# licheepi_nano_pcb.net
KiCad netlist of a schematic drawn in Altium Designer
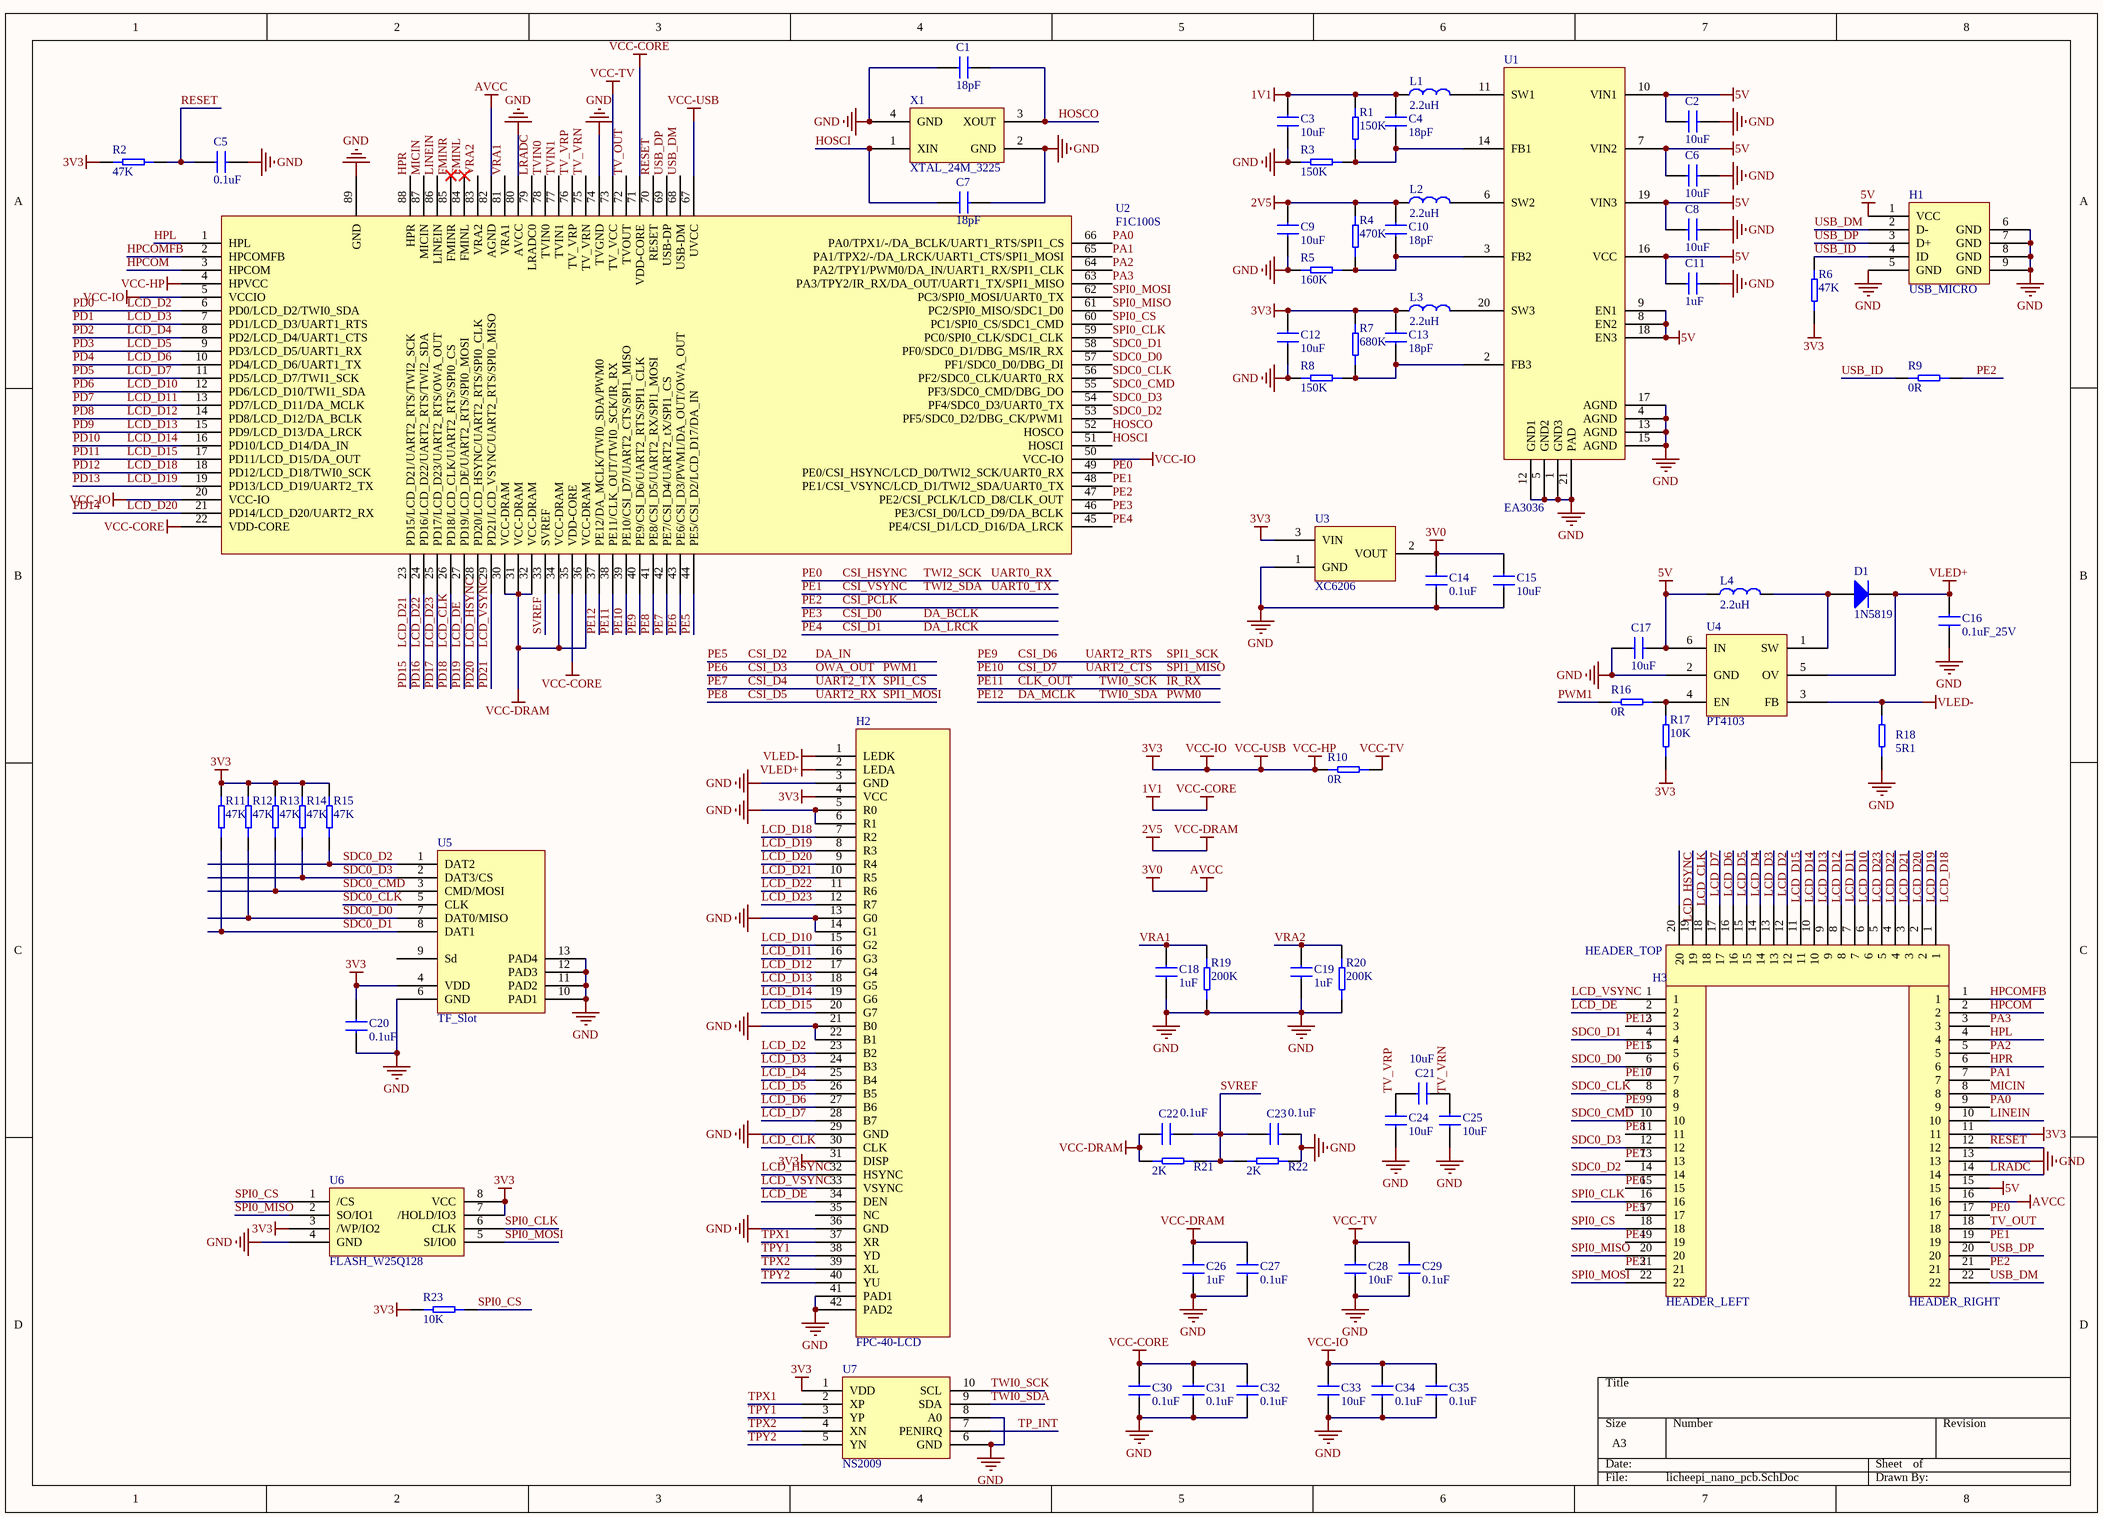
[diagram p0: licheepi_nano_pcb.SchDoc]

(export (version "E")
  (design (tool "Eeschema 10.0.6"))
  (components
    (comp (ref "C1")
      (value "18pF")
      (footprint "0402C")
      (description "SMD-CAP")
      (libsource (lib "licheepi_nano_pcb") (part "CAP"))
    )
    (comp (ref "C2")
      (value "10uF")
      (footprint "0402C")
      (description "SMD-CAP")
      (libsource (lib "licheepi_nano_pcb") (part "CAP"))
    )
    (comp (ref "C3")
      (value "10uF")
      (footprint "0402C")
      (description "SMD-CAP")
      (libsource (lib "licheepi_nano_pcb") (part "CAP"))
    )
    (comp (ref "C4")
      (value "18pF")
      (footprint "0402C")
      (description "SMD-CAP")
      (libsource (lib "licheepi_nano_pcb") (part "CAP"))
    )
    (comp (ref "C5")
      (value "0.1uF")
      (footprint "0402C")
      (description "SMD-CAP")
      (libsource (lib "licheepi_nano_pcb") (part "CAP"))
    )
    (comp (ref "C6")
      (value "10uF")
      (footprint "0402C")
      (description "SMD-CAP")
      (libsource (lib "licheepi_nano_pcb") (part "CAP"))
    )
    (comp (ref "C7")
      (value "18pF")
      (footprint "0402C")
      (description "SMD-CAP")
      (libsource (lib "licheepi_nano_pcb") (part "CAP"))
    )
    (comp (ref "C8")
      (value "10uF")
      (footprint "0402C")
      (description "SMD-CAP")
      (libsource (lib "licheepi_nano_pcb") (part "CAP"))
    )
    (comp (ref "C9")
      (value "10uF")
      (footprint "0402C")
      (description "SMD-CAP")
      (libsource (lib "licheepi_nano_pcb") (part "CAP"))
    )
    (comp (ref "C10")
      (value "18pF")
      (footprint "0402C")
      (description "SMD-CAP")
      (libsource (lib "licheepi_nano_pcb") (part "CAP"))
    )
    (comp (ref "C11")
      (value "1uF")
      (footprint "0402C")
      (description "SMD-CAP")
      (libsource (lib "licheepi_nano_pcb") (part "CAP"))
    )
    (comp (ref "C12")
      (value "10uF")
      (footprint "0402C")
      (description "SMD-CAP")
      (libsource (lib "licheepi_nano_pcb") (part "CAP"))
    )
    (comp (ref "C13")
      (value "18pF")
      (footprint "0402C")
      (description "SMD-CAP")
      (libsource (lib "licheepi_nano_pcb") (part "CAP"))
    )
    (comp (ref "C14")
      (value "0.1uF")
      (footprint "0402C")
      (description "SMD-CAP")
      (libsource (lib "licheepi_nano_pcb") (part "CAP"))
    )
    (comp (ref "C15")
      (value "10uF")
      (footprint "0402C")
      (description "SMD-CAP")
      (libsource (lib "licheepi_nano_pcb") (part "CAP"))
    )
    (comp (ref "C16")
      (value "0.1uF_25V")
      (footprint "0402C")
      (description "SMD-CAP")
      (libsource (lib "licheepi_nano_pcb") (part "CAP"))
    )
    (comp (ref "C17")
      (value "10uF")
      (footprint "0402C")
      (description "SMD-CAP")
      (libsource (lib "licheepi_nano_pcb") (part "CAP"))
    )
    (comp (ref "C18")
      (value "1uF")
      (footprint "0402C")
      (description "SMD-CAP")
      (libsource (lib "licheepi_nano_pcb") (part "CAP"))
    )
    (comp (ref "C19")
      (value "1uF")
      (footprint "0402C")
      (description "SMD-CAP")
      (libsource (lib "licheepi_nano_pcb") (part "CAP"))
    )
    (comp (ref "C20")
      (value "0.1uF")
      (footprint "0402C")
      (description "SMD-CAP")
      (libsource (lib "licheepi_nano_pcb") (part "CAP"))
    )
    (comp (ref "C21")
      (value "10uF")
      (footprint "0402C")
      (description "SMD-CAP")
      (libsource (lib "licheepi_nano_pcb") (part "CAP"))
    )
    (comp (ref "C22")
      (value "0.1uF")
      (footprint "0402C")
      (description "SMD-CAP")
      (libsource (lib "licheepi_nano_pcb") (part "CAP"))
    )
    (comp (ref "C23")
      (value "0.1uF")
      (footprint "0402C")
      (description "SMD-CAP")
      (libsource (lib "licheepi_nano_pcb") (part "CAP"))
    )
    (comp (ref "C24")
      (value "10uF")
      (footprint "0402C")
      (description "SMD-CAP")
      (libsource (lib "licheepi_nano_pcb") (part "CAP"))
    )
    (comp (ref "C25")
      (value "10uF")
      (footprint "0402C")
      (description "SMD-CAP")
      (libsource (lib "licheepi_nano_pcb") (part "CAP"))
    )
    (comp (ref "C26")
      (value "1uF")
      (footprint "0402C")
      (description "SMD-CAP")
      (libsource (lib "licheepi_nano_pcb") (part "CAP"))
    )
    (comp (ref "C27")
      (value "0.1uF")
      (footprint "0402C")
      (description "SMD-CAP")
      (libsource (lib "licheepi_nano_pcb") (part "CAP"))
    )
    (comp (ref "C28")
      (value "10uF")
      (footprint "0402C")
      (description "SMD-CAP")
      (libsource (lib "licheepi_nano_pcb") (part "CAP"))
    )
    (comp (ref "C29")
      (value "0.1uF")
      (footprint "0402C")
      (description "SMD-CAP")
      (libsource (lib "licheepi_nano_pcb") (part "CAP"))
    )
    (comp (ref "C30")
      (value "0.1uF")
      (footprint "0402C")
      (description "SMD-CAP")
      (libsource (lib "licheepi_nano_pcb") (part "CAP"))
    )
    (comp (ref "C31")
      (value "0.1uF")
      (footprint "0402C")
      (description "SMD-CAP")
      (libsource (lib "licheepi_nano_pcb") (part "CAP"))
    )
    (comp (ref "C32")
      (value "0.1uF")
      (footprint "0402C")
      (description "SMD-CAP")
      (libsource (lib "licheepi_nano_pcb") (part "CAP"))
    )
    (comp (ref "C33")
      (value "10uF")
      (footprint "0402C")
      (description "SMD-CAP")
      (libsource (lib "licheepi_nano_pcb") (part "CAP"))
    )
    (comp (ref "C34")
      (value "0.1uF")
      (footprint "0402C")
      (description "SMD-CAP")
      (libsource (lib "licheepi_nano_pcb") (part "CAP"))
    )
    (comp (ref "C35")
      (value "0.1uF")
      (footprint "0402C")
      (description "SMD-CAP")
      (libsource (lib "licheepi_nano_pcb") (part "CAP"))
    )
    (comp (ref "D1")
      (value "1N5819")
      (footprint "SOD123")
      (libsource (lib "licheepi_nano_pcb") (part "1N5819"))
    )
    (comp (ref "H1")
      (value "USB_MICRO")
      (footprint "USB_MICRO_insert")
      (libsource (lib "licheepi_nano_pcb") (part "USB_MICRO"))
    )
    (comp (ref "H2")
      (value "FPC-40-LCD")
      (footprint "FPC-40P-0.5")
      (libsource (lib "licheepi_nano_pcb") (part "FPC-40-LCD"))
    )
    (comp (ref "H3")
      (value "HEADER_TOP")
      (footprint "SIP20_1.27_half")
      (libsource (lib "licheepi_nano_pcb") (part "HEADER_TOP"))
    )
    (comp (ref "H4")
      (value "HEADER_LEFT")
      (footprint "SIP22_10_1.27-mir")
      (libsource (lib "licheepi_nano_pcb") (part "HEADER_LEFT"))
    )
    (comp (ref "H5")
      (value "HEADER_RIGHT")
      (footprint "SIP22_10_1.27")
      (libsource (lib "licheepi_nano_pcb") (part "HEADER_RIGHT"))
    )
    (comp (ref "L1")
      (value "2.2uH")
      (footprint "CD32")
      (description "电感")
      (libsource (lib "licheepi_nano_pcb") (part "L1"))
    )
    (comp (ref "L2")
      (value "2.2uH")
      (footprint "CD32")
      (description "电感")
      (libsource (lib "licheepi_nano_pcb") (part "L1"))
    )
    (comp (ref "L3")
      (value "2.2uH")
      (footprint "CD32")
      (description "电感")
      (libsource (lib "licheepi_nano_pcb") (part "L1"))
    )
    (comp (ref "L4")
      (value "2.2uH")
      (footprint "CD32")
      (description "电感")
      (libsource (lib "licheepi_nano_pcb") (part "L1"))
    )
    (comp (ref "R1") (value "150K") (footprint "0402R") (libsource (lib "licheepi_nano_pcb") (part "R")))
    (comp (ref "R2") (value "47K") (footprint "0402R") (libsource (lib "licheepi_nano_pcb") (part "R")))
    (comp (ref "R3") (value "150K") (footprint "0402R") (libsource (lib "licheepi_nano_pcb") (part "R")))
    (comp (ref "R4") (value "470K") (footprint "0402R") (libsource (lib "licheepi_nano_pcb") (part "R")))
    (comp (ref "R5") (value "160K") (footprint "0402R") (libsource (lib "licheepi_nano_pcb") (part "R")))
    (comp (ref "R6") (value "47K") (footprint "0402R") (libsource (lib "licheepi_nano_pcb") (part "R")))
    (comp (ref "R7") (value "680K") (footprint "0402R") (libsource (lib "licheepi_nano_pcb") (part "R")))
    (comp (ref "R8") (value "150K") (footprint "0402R") (libsource (lib "licheepi_nano_pcb") (part "R")))
    (comp (ref "R9") (value "0R") (footprint "0402R") (libsource (lib "licheepi_nano_pcb") (part "R")))
    (comp (ref "R10") (value "0R") (footprint "0402R") (libsource (lib "licheepi_nano_pcb") (part "R")))
    (comp (ref "R11") (value "47K") (footprint "0402R") (libsource (lib "licheepi_nano_pcb") (part "R")))
    (comp (ref "R12") (value "47K") (footprint "0402R") (libsource (lib "licheepi_nano_pcb") (part "R")))
    (comp (ref "R13") (value "47K") (footprint "0402R") (libsource (lib "licheepi_nano_pcb") (part "R")))
    (comp (ref "R14") (value "47K") (footprint "0402R") (libsource (lib "licheepi_nano_pcb") (part "R")))
    (comp (ref "R15") (value "47K") (footprint "0402R") (libsource (lib "licheepi_nano_pcb") (part "R")))
    (comp (ref "R16") (value "0R") (footprint "0402R") (libsource (lib "licheepi_nano_pcb") (part "R")))
    (comp (ref "R17") (value "10K") (footprint "0402R") (libsource (lib "licheepi_nano_pcb") (part "R")))
    (comp (ref "R18") (value "5R1") (footprint "0402R") (libsource (lib "licheepi_nano_pcb") (part "R")))
    (comp (ref "R19") (value "200K") (footprint "0402R") (libsource (lib "licheepi_nano_pcb") (part "R")))
    (comp (ref "R20") (value "200K") (footprint "0402R") (libsource (lib "licheepi_nano_pcb") (part "R")))
    (comp (ref "R21") (value "2K") (footprint "0402R") (libsource (lib "licheepi_nano_pcb") (part "R")))
    (comp (ref "R22") (value "2K") (footprint "0402R") (libsource (lib "licheepi_nano_pcb") (part "R")))
    (comp (ref "R23") (value "10K") (footprint "0402R") (libsource (lib "licheepi_nano_pcb") (part "R")))
    (comp (ref "U1")
      (value "EA3036")
      (footprint "QFN20-3x3")
      (libsource (lib "licheepi_nano_pcb") (part "EA3036"))
    )
    (comp (ref "U2")
      (value "F1C100S")
      (footprint "QFN88-0.4")
      (libsource (lib "licheepi_nano_pcb") (part "F1C100S"))
    )
    (comp (ref "U3")
      (value "XC6206")
      (footprint "SOT-23")
      (libsource (lib "licheepi_nano_pcb") (part "XC6206"))
    )
    (comp (ref "U4")
      (value "PT4103")
      (footprint "sot23_6")
      (libsource (lib "licheepi_nano_pcb") (part "PT4103"))
    )
    (comp (ref "U5")
      (value "TF_Slot")
      (footprint "TF_self-eject")
      (libsource (lib "licheepi_nano_pcb") (part "TF_Slot"))
    )
    (comp (ref "U6")
      (value "FLASH_W25Q128")
      (footprint "SO-8M")
      (libsource (lib "licheepi_nano_pcb") (part "FLASH_W25Q128"))
    )
    (comp (ref "U7")
      (value "NS2009")
      (footprint "MSOP10")
      (libsource (lib "licheepi_nano_pcb") (part "NS2009"))
    )
    (comp (ref "X1")
      (value "XTAL_24M_3225")
      (footprint "SMD_3225")
      (libsource (lib "licheepi_nano_pcb") (part "XTAL_24M_3225"))
    )
  )
  (nets
    (net (code "1") (name "/CLK_OUT") (class "Default")
      (node (ref "H4") (pin "5") (pinfunction "5_5") (pintype "passive"))
      (node (ref "U2") (pin "38") (pinfunction "PE11/CLK_OUT/TWI0_SCK/IR_RX_38") (pintype "passive"))
      (node (ref "U7") (pin "10") (pinfunction "SCL_10") (pintype "passive"))
    )
    (net (code "2") (name "/CSI_D0") (class "Default")
      (node (ref "H4") (pin "21") (pinfunction "21_21") (pintype "passive"))
      (node (ref "U2") (pin "46") (pinfunction "PE3/CSI_D0/LCD_D9/DA_BCLK_46") (pintype "passive"))
    )
    (net (code "3") (name "/CSI_D1") (class "Default")
      (node (ref "H4") (pin "19") (pinfunction "19_19") (pintype "passive"))
      (node (ref "U2") (pin "45") (pinfunction "PE4/CSI_D1/LCD_D16/DA_LRCK_45") (pintype "passive"))
    )
    (net (code "4") (name "/CSI_D2") (class "Default")
      (node (ref "H4") (pin "17") (pinfunction "17_17") (pintype "passive"))
      (node (ref "U2") (pin "44") (pinfunction "PE5/CSI_D2/LCD_D17/DA_IN_44") (pintype "passive"))
    )
    (net (code "5") (name "/CSI_D3") (class "Default")
      (node (ref "H4") (pin "15") (pinfunction "15_15") (pintype "passive"))
      (node (ref "R16") (pin "1") (pinfunction "1_1") (pintype "passive"))
      (node (ref "U2") (pin "43") (pinfunction "PE6/CSI_D3/PWM1/DA_OUT/OWA_OUT_43") (pintype "passive"))
    )
    (net (code "6") (name "/CSI_D4") (class "Default")
      (node (ref "H4") (pin "13") (pinfunction "13_13") (pintype "passive"))
      (node (ref "U2") (pin "42") (pinfunction "PE7/CSI_D4/UART2_tX/SPI1_CS_42") (pintype "passive"))
    )
    (net (code "7") (name "/CSI_D5") (class "Default")
      (node (ref "H4") (pin "11") (pinfunction "11_11") (pintype "passive"))
      (node (ref "U2") (pin "41") (pinfunction "PE8/CSI_D5/UART2_RX/SPI1_MOSI_41") (pintype "passive"))
    )
    (net (code "8") (name "/CSI_D6") (class "Default")
      (node (ref "H4") (pin "9") (pinfunction "9_9") (pintype "passive"))
      (node (ref "U2") (pin "40") (pinfunction "PE9/CSI_D6/UART2_RTS/SPI1_CLK_40") (pintype "passive"))
    )
    (net (code "9") (name "/CSI_D7") (class "Default")
      (node (ref "H4") (pin "7") (pinfunction "7_7") (pintype "passive"))
      (node (ref "U2") (pin "39") (pinfunction "PE10/CSI_D7/UART2_CTS/SPI1_MISO_39") (pintype "passive"))
    )
    (net (code "10") (name "/CSI_HSYNC") (class "Default")
      (node (ref "H5") (pin "17") (pinfunction "17_17") (pintype "passive"))
      (node (ref "U2") (pin "49") (pinfunction "PE0/CSI_HSYNC/LCD_D0/TWI2_SCK/UART0_RX_49") (pintype "passive"))
    )
    (net (code "11") (name "/CSI_PCLK") (class "Default")
      (node (ref "H5") (pin "21") (pinfunction "21_21") (pintype "passive"))
      (node (ref "R9") (pin "2") (pinfunction "2_2") (pintype "passive"))
      (node (ref "U2") (pin "47") (pinfunction "PE2/CSI_PCLK/LCD_D8/CLK_OUT_47") (pintype "passive"))
    )
    (net (code "12") (name "/CSI_VSYNC") (class "Default")
      (node (ref "H5") (pin "19") (pinfunction "19_19") (pintype "passive"))
      (node (ref "U2") (pin "48") (pinfunction "PE1/CSI_VSYNC/LCD_D1/TWI2_SDA/UART0_TX_48") (pintype "passive"))
    )
    (net (code "13") (name "/DA_MCLK") (class "Default")
      (node (ref "H4") (pin "3") (pinfunction "3_3") (pintype "passive"))
      (node (ref "U2") (pin "37") (pinfunction "PE12/DA_MCLK/TWI0_SDA/PWM0_37") (pintype "passive"))
      (node (ref "U7") (pin "9") (pinfunction "SDA_9") (pintype "passive"))
    )
    (net (code "14") (name "/FMINL") (class "Default")
      (node (ref "U2") (pin "84") (pinfunction "FMINL_84") (pintype "passive+no_connect"))
    )
    (net (code "15") (name "/FMINR") (class "Default")
      (node (ref "U2") (pin "85") (pinfunction "FMINR_85") (pintype "passive+no_connect"))
    )
    (net (code "16") (name "/HOSCI") (class "Default")
      (node (ref "C7") (pin "1") (pinfunction "1_1") (pintype "passive"))
      (node (ref "U2") (pin "51") (pinfunction "HOSCI_51") (pintype "passive"))
      (node (ref "X1") (pin "1") (pinfunction "XIN_1") (pintype "passive"))
    )
    (net (code "17") (name "/HOSCO") (class "Default")
      (node (ref "C1") (pin "2") (pinfunction "2_2") (pintype "passive"))
      (node (ref "U2") (pin "52") (pinfunction "HOSCO_52") (pintype "passive"))
      (node (ref "X1") (pin "3") (pinfunction "XOUT_3") (pintype "passive"))
    )
    (net (code "18") (name "/HPCOM") (class "Default")
      (node (ref "H5") (pin "2") (pinfunction "2_2") (pintype "passive"))
      (node (ref "U2") (pin "3") (pinfunction "HPCOM_3") (pintype "passive"))
    )
    (net (code "19") (name "/HPCOMFB") (class "Default")
      (node (ref "H5") (pin "1") (pinfunction "1_1") (pintype "passive"))
      (node (ref "U2") (pin "2") (pinfunction "HPCOMFB_2") (pintype "passive"))
    )
    (net (code "20") (name "/HPL") (class "Default")
      (node (ref "H5") (pin "4") (pinfunction "4_4") (pintype "passive"))
      (node (ref "U2") (pin "1") (pinfunction "HPL_1") (pintype "passive"))
    )
    (net (code "21") (name "/HPR") (class "Default")
      (node (ref "H5") (pin "6") (pinfunction "6_6") (pintype "passive"))
      (node (ref "U2") (pin "88") (pinfunction "HPR_88") (pintype "passive"))
    )
    (net (code "22") (name "/LCD_CLK") (class "Default")
      (node (ref "H2") (pin "30") (pinfunction "CLK_30") (pintype "passive"))
      (node (ref "H3") (pin "19") (pinfunction "19_19") (pintype "passive"))
      (node (ref "U2") (pin "26") (pinfunction "PD18/LCD_CLK/UART2_RTS/SPI0_CS_26") (pintype "passive"))
    )
    (net (code "23") (name "/LCD_D2") (class "Default")
      (node (ref "H2") (pin "23") (pinfunction "B2_23") (pintype "passive"))
      (node (ref "H3") (pin "13") (pinfunction "13_13") (pintype "passive"))
      (node (ref "U2") (pin "6") (pinfunction "PD0/LCD_D2/TWI0_SDA_6") (pintype "passive"))
    )
    (net (code "24") (name "/LCD_D3") (class "Default")
      (node (ref "H2") (pin "24") (pinfunction "B3_24") (pintype "passive"))
      (node (ref "H3") (pin "14") (pinfunction "14_14") (pintype "passive"))
      (node (ref "U2") (pin "7") (pinfunction "PD1/LCD_D3/UART1_RTS_7") (pintype "passive"))
    )
    (net (code "25") (name "/LCD_D4") (class "Default")
      (node (ref "H2") (pin "25") (pinfunction "B4_25") (pintype "passive"))
      (node (ref "H3") (pin "15") (pinfunction "15_15") (pintype "passive"))
      (node (ref "U2") (pin "8") (pinfunction "PD2/LCD_D4/UART1_CTS_8") (pintype "passive"))
    )
    (net (code "26") (name "/LCD_D5") (class "Default")
      (node (ref "H2") (pin "26") (pinfunction "B5_26") (pintype "passive"))
      (node (ref "H3") (pin "16") (pinfunction "16_16") (pintype "passive"))
      (node (ref "U2") (pin "9") (pinfunction "PD3/LCD_D5/UART1_RX_9") (pintype "passive"))
    )
    (net (code "27") (name "/LCD_D6") (class "Default")
      (node (ref "H2") (pin "27") (pinfunction "B6_27") (pintype "passive"))
      (node (ref "H3") (pin "17") (pinfunction "17_17") (pintype "passive"))
      (node (ref "U2") (pin "10") (pinfunction "PD4/LCD_D6/UART1_TX_10") (pintype "passive"))
    )
    (net (code "28") (name "/LCD_D7") (class "Default")
      (node (ref "H2") (pin "28") (pinfunction "B7_28") (pintype "passive"))
      (node (ref "H3") (pin "18") (pinfunction "18_18") (pintype "passive"))
      (node (ref "U2") (pin "11") (pinfunction "PD5/LCD_D7/TWI1_SCK_11") (pintype "passive"))
    )
    (net (code "29") (name "/LCD_D10") (class "Default")
      (node (ref "H2") (pin "15") (pinfunction "G2_15") (pintype "passive"))
      (node (ref "H3") (pin "7") (pinfunction "7_7") (pintype "passive"))
      (node (ref "U2") (pin "12") (pinfunction "PD6/LCD_D10/TWI1_SDA_12") (pintype "passive"))
    )
    (net (code "30") (name "/LCD_D11") (class "Default")
      (node (ref "H2") (pin "16") (pinfunction "G3_16") (pintype "passive"))
      (node (ref "H3") (pin "8") (pinfunction "8_8") (pintype "passive"))
      (node (ref "U2") (pin "13") (pinfunction "PD7/LCD_D11/DA_MCLK_13") (pintype "passive"))
    )
    (net (code "31") (name "/LCD_D12") (class "Default")
      (node (ref "H2") (pin "17") (pinfunction "G4_17") (pintype "passive"))
      (node (ref "H3") (pin "9") (pinfunction "9_9") (pintype "passive"))
      (node (ref "U2") (pin "14") (pinfunction "PD8/LCD_D12/DA_BCLK_14") (pintype "passive"))
    )
    (net (code "32") (name "/LCD_D13") (class "Default")
      (node (ref "H2") (pin "18") (pinfunction "G5_18") (pintype "passive"))
      (node (ref "H3") (pin "10") (pinfunction "10_10") (pintype "passive"))
      (node (ref "U2") (pin "15") (pinfunction "PD9/LCD_D13/DA_LRCK_15") (pintype "passive"))
    )
    (net (code "33") (name "/LCD_D14") (class "Default")
      (node (ref "H2") (pin "19") (pinfunction "G6_19") (pintype "passive"))
      (node (ref "H3") (pin "11") (pinfunction "11_11") (pintype "passive"))
      (node (ref "U2") (pin "16") (pinfunction "PD10/LCD_D14/DA_IN_16") (pintype "passive"))
    )
    (net (code "34") (name "/LCD_D15") (class "Default")
      (node (ref "H2") (pin "20") (pinfunction "G7_20") (pintype "passive"))
      (node (ref "H3") (pin "12") (pinfunction "12_12") (pintype "passive"))
      (node (ref "U2") (pin "17") (pinfunction "PD11/LCD_D15/DA_OUT_17") (pintype "passive"))
    )
    (net (code "35") (name "/LCD_D18") (class "Default")
      (node (ref "H2") (pin "7") (pinfunction "R2_7") (pintype "passive"))
      (node (ref "H3") (pin "1") (pinfunction "1_1") (pintype "passive"))
      (node (ref "U2") (pin "18") (pinfunction "PD12/LCD_D18/TWI0_SCK_18") (pintype "passive"))
    )
    (net (code "36") (name "/LCD_D19") (class "Default")
      (node (ref "H2") (pin "8") (pinfunction "R3_8") (pintype "passive"))
      (node (ref "H3") (pin "2") (pinfunction "2_2") (pintype "passive"))
      (node (ref "U2") (pin "19") (pinfunction "PD13/LCD_D19/UART2_TX_19") (pintype "passive"))
    )
    (net (code "37") (name "/LCD_D20") (class "Default")
      (node (ref "H2") (pin "9") (pinfunction "R4_9") (pintype "passive"))
      (node (ref "H3") (pin "3") (pinfunction "3_3") (pintype "passive"))
      (node (ref "U2") (pin "21") (pinfunction "PD14/LCD_D20/UART2_RX_21") (pintype "passive"))
    )
    (net (code "38") (name "/LCD_D21") (class "Default")
      (node (ref "H2") (pin "10") (pinfunction "R5_10") (pintype "passive"))
      (node (ref "H3") (pin "4") (pinfunction "4_4") (pintype "passive"))
      (node (ref "U2") (pin "23") (pinfunction "PD15/LCD_D21/UART2_RTS/TWI2_SCK_23") (pintype "passive"))
    )
    (net (code "39") (name "/LCD_D22") (class "Default")
      (node (ref "H2") (pin "11") (pinfunction "R6_11") (pintype "passive"))
      (node (ref "H3") (pin "5") (pinfunction "5_5") (pintype "passive"))
      (node (ref "U2") (pin "24") (pinfunction "PD16/LCD_D22/UART2_RTS/TWI2_SDA_24") (pintype "passive"))
    )
    (net (code "40") (name "/LCD_D23") (class "Default")
      (node (ref "H2") (pin "12") (pinfunction "R7_12") (pintype "passive"))
      (node (ref "H3") (pin "6") (pinfunction "6_6") (pintype "passive"))
      (node (ref "U2") (pin "25") (pinfunction "PD17/LCD_D23/UART2_RTS/OWA_OUT_25") (pintype "passive"))
    )
    (net (code "41") (name "/LCD_DE") (class "Default")
      (node (ref "H2") (pin "34") (pinfunction "DEN_34") (pintype "passive"))
      (node (ref "H4") (pin "2") (pinfunction "2_2") (pintype "passive"))
      (node (ref "U2") (pin "27") (pinfunction "PD19/LCD_DE/UART2_RTS/SPI0_MOSI_27") (pintype "passive"))
    )
    (net (code "42") (name "/LCD_HSYNC") (class "Default")
      (node (ref "H2") (pin "32") (pinfunction "HSYNC_32") (pintype "passive"))
      (node (ref "H3") (pin "20") (pinfunction "20_20") (pintype "passive"))
      (node (ref "U2") (pin "28") (pinfunction "PD20/LCD_HSYNC/UART2_RTS/SPI0_CLK_28") (pintype "passive"))
    )
    (net (code "43") (name "/LCD_VSYNC") (class "Default")
      (node (ref "H2") (pin "33") (pinfunction "VSYNC_33") (pintype "passive"))
      (node (ref "H4") (pin "1") (pinfunction "1_1") (pintype "passive"))
      (node (ref "U2") (pin "29") (pinfunction "PD21/LCD_VSYNC/UART2_RTS/SPI0_MISO_29") (pintype "passive"))
    )
    (net (code "44") (name "/LINEIN") (class "Default")
      (node (ref "H5") (pin "10") (pinfunction "10_10") (pintype "passive"))
      (node (ref "U2") (pin "86") (pinfunction "LINEIN_86") (pintype "passive"))
    )
    (net (code "45") (name "/LRADC") (class "Default")
      (node (ref "H5") (pin "14") (pinfunction "14_14") (pintype "passive"))
      (node (ref "U2") (pin "79") (pinfunction "LRADC0_79") (pintype "passive"))
    )
    (net (code "46") (name "/MICIN") (class "Default")
      (node (ref "H5") (pin "8") (pinfunction "8_8") (pintype "passive"))
      (node (ref "U2") (pin "87") (pinfunction "MICIN_87") (pintype "passive"))
    )
    (net (code "47") (name "/PA0") (class "Default")
      (node (ref "H5") (pin "9") (pinfunction "9_9") (pintype "passive"))
      (node (ref "U2") (pin "66") (pinfunction "PA0/TPX1/-/DA_BCLK/UART1_RTS/SPI1_CS_66") (pintype "passive"))
    )
    (net (code "48") (name "/PA1") (class "Default")
      (node (ref "H5") (pin "7") (pinfunction "7_7") (pintype "passive"))
      (node (ref "U2") (pin "65") (pinfunction "PA1/TPX2/-/DA_LRCK/UART1_CTS/SPI1_MOSI_65") (pintype "passive"))
    )
    (net (code "49") (name "/PA2") (class "Default")
      (node (ref "H5") (pin "5") (pinfunction "5_5") (pintype "passive"))
      (node (ref "U2") (pin "64") (pinfunction "PA2/TPY1/PWM0/DA_IN/UART1_RX/SPI1_CLK_64") (pintype "passive"))
    )
    (net (code "50") (name "/PA3") (class "Default")
      (node (ref "H5") (pin "3") (pinfunction "3_3") (pintype "passive"))
      (node (ref "U2") (pin "63") (pinfunction "PA3/TPY2/IR_RX/DA_OUT/UART1_TX/SPI1_MISO_63") (pintype "passive"))
    )
    (net (code "51") (name "/RESET") (class "Default")
      (node (ref "C5") (pin "1") (pinfunction "1_1") (pintype "passive"))
      (node (ref "H5") (pin "12") (pinfunction "12_12") (pintype "passive"))
      (node (ref "R2") (pin "2") (pinfunction "2_2") (pintype "passive"))
      (node (ref "U2") (pin "70") (pinfunction "RESET_70") (pintype "passive"))
    )
    (net (code "52") (name "/SDC0_CLK") (class "Default")
      (node (ref "H4") (pin "8") (pinfunction "8_8") (pintype "passive"))
      (node (ref "U2") (pin "56") (pinfunction "PF2/SDC0_CLK/UART0_RX_56") (pintype "passive"))
      (node (ref "U5") (pin "5") (pinfunction "CLK_5") (pintype "passive"))
    )
    (net (code "53") (name "/SDC0_CMD") (class "Default")
      (node (ref "H4") (pin "10") (pinfunction "10_10") (pintype "passive"))
      (node (ref "R13") (pin "1") (pinfunction "1_1") (pintype "passive"))
      (node (ref "U2") (pin "55") (pinfunction "PF3/SDC0_CMD/DBG_DO_55") (pintype "passive"))
      (node (ref "U5") (pin "3") (pinfunction "CMD/MOSI_3") (pintype "passive"))
    )
    (net (code "54") (name "/SDC0_D0") (class "Default")
      (node (ref "H4") (pin "6") (pinfunction "6_6") (pintype "passive"))
      (node (ref "R12") (pin "1") (pinfunction "1_1") (pintype "passive"))
      (node (ref "U2") (pin "57") (pinfunction "PF1/SDC0_D0/DBG_DI_57") (pintype "passive"))
      (node (ref "U5") (pin "7") (pinfunction "DAT0/MISO_7") (pintype "passive"))
    )
    (net (code "55") (name "/SDC0_D1") (class "Default")
      (node (ref "H4") (pin "4") (pinfunction "4_4") (pintype "passive"))
      (node (ref "R11") (pin "1") (pinfunction "1_1") (pintype "passive"))
      (node (ref "U2") (pin "58") (pinfunction "PF0/SDC0_D1/DBG_MS/IR_RX_58") (pintype "passive"))
      (node (ref "U5") (pin "8") (pinfunction "DAT1_8") (pintype "passive"))
    )
    (net (code "56") (name "/SDC0_D2") (class "Default")
      (node (ref "H4") (pin "14") (pinfunction "14_14") (pintype "passive"))
      (node (ref "R15") (pin "1") (pinfunction "1_1") (pintype "passive"))
      (node (ref "U2") (pin "53") (pinfunction "PF5/SDC0_D2/DBG_CK/PWM1_53") (pintype "passive"))
      (node (ref "U5") (pin "1") (pinfunction "DAT2_1") (pintype "passive"))
    )
    (net (code "57") (name "/SDC0_D3") (class "Default")
      (node (ref "H4") (pin "12") (pinfunction "12_12") (pintype "passive"))
      (node (ref "R14") (pin "1") (pinfunction "1_1") (pintype "passive"))
      (node (ref "U2") (pin "54") (pinfunction "PF4/SDC0_D3/UART0_TX_54") (pintype "passive"))
      (node (ref "U5") (pin "2") (pinfunction "DAT3/CS_2") (pintype "passive"))
    )
    (net (code "58") (name "/SPI0_CLK") (class "Default")
      (node (ref "H4") (pin "16") (pinfunction "16_16") (pintype "passive"))
      (node (ref "U2") (pin "59") (pinfunction "PC0/SPI0_CLK/SDC1_CLK_59") (pintype "passive"))
      (node (ref "U6") (pin "6") (pinfunction "CLK_6") (pintype "passive"))
    )
    (net (code "59") (name "/SPI0_CS") (class "Default")
      (node (ref "H4") (pin "18") (pinfunction "18_18") (pintype "passive"))
      (node (ref "R23") (pin "2") (pinfunction "2_2") (pintype "passive"))
      (node (ref "U2") (pin "60") (pinfunction "PC1/SPI0_CS/SDC1_CMD_60") (pintype "passive"))
      (node (ref "U6") (pin "1") (pinfunction "/CS_1") (pintype "passive"))
    )
    (net (code "60") (name "/SPI0_MISO") (class "Default")
      (node (ref "H4") (pin "20") (pinfunction "20_20") (pintype "passive"))
      (node (ref "U2") (pin "61") (pinfunction "PC2/SPI0_MISO/SDC1_D0_61") (pintype "passive"))
      (node (ref "U6") (pin "2") (pinfunction "SO/IO1_2") (pintype "passive"))
    )
    (net (code "61") (name "/SPI0_MOSI") (class "Default")
      (node (ref "H4") (pin "22") (pinfunction "22_22") (pintype "passive"))
      (node (ref "U2") (pin "62") (pinfunction "PC3/SPI0_MOSI/UART0_TX_62") (pintype "passive"))
      (node (ref "U6") (pin "5") (pinfunction "SI/IO0_5") (pintype "passive"))
    )
    (net (code "62") (name "/SVREF") (class "Default")
      (node (ref "C22") (pin "2") (pinfunction "2_2") (pintype "passive"))
      (node (ref "C23") (pin "1") (pinfunction "1_1") (pintype "passive"))
      (node (ref "R21") (pin "1") (pinfunction "1_1") (pintype "passive"))
      (node (ref "R22") (pin "2") (pinfunction "2_2") (pintype "passive"))
      (node (ref "U2") (pin "33") (pinfunction "SVREF_33") (pintype "passive"))
    )
    (net (code "63") (name "/TPX1") (class "Default")
      (node (ref "H2") (pin "37") (pinfunction "XR_37") (pintype "passive"))
      (node (ref "U7") (pin "2") (pinfunction "XP_2") (pintype "passive"))
    )
    (net (code "64") (name "/TPX2") (class "Default")
      (node (ref "H2") (pin "39") (pinfunction "XL_39") (pintype "passive"))
      (node (ref "U7") (pin "4") (pinfunction "XN_4") (pintype "passive"))
    )
    (net (code "65") (name "/TPY1") (class "Default")
      (node (ref "H2") (pin "38") (pinfunction "YD_38") (pintype "passive"))
      (node (ref "U7") (pin "3") (pinfunction "YP_3") (pintype "passive"))
    )
    (net (code "66") (name "/TPY2") (class "Default")
      (node (ref "H2") (pin "40") (pinfunction "YU_40") (pintype "passive"))
      (node (ref "U7") (pin "5") (pinfunction "YN_5") (pintype "passive"))
    )
    (net (code "67") (name "/TP_INT") (class "Default")
      (node (ref "U7") (pin "7") (pinfunction "PENIRQ_7") (pintype "passive"))
    )
    (net (code "68") (name "/TVIN0") (class "Default")
      (node (ref "U2") (pin "78") (pinfunction "TVIN0_78") (pintype "passive"))
    )
    (net (code "69") (name "/TVIN1") (class "Default")
      (node (ref "U2") (pin "77") (pinfunction "TVIN1_77") (pintype "passive"))
    )
    (net (code "70") (name "/TV_OUT") (class "Default")
      (node (ref "H5") (pin "18") (pinfunction "18_18") (pintype "passive"))
      (node (ref "U2") (pin "72") (pinfunction "TVOUT_72") (pintype "passive"))
    )
    (net (code "71") (name "/TV_VRN") (class "Default")
      (node (ref "C21") (pin "2") (pinfunction "2_2") (pintype "passive"))
      (node (ref "C25") (pin "1") (pinfunction "1_1") (pintype "passive"))
      (node (ref "U2") (pin "75") (pinfunction "TV_VRN_75") (pintype "passive"))
    )
    (net (code "72") (name "/TV_VRP") (class "Default")
      (node (ref "C21") (pin "1") (pinfunction "1_1") (pintype "passive"))
      (node (ref "C24") (pin "1") (pinfunction "1_1") (pintype "passive"))
      (node (ref "U2") (pin "76") (pinfunction "TV_VRP_76") (pintype "passive"))
    )
    (net (code "73") (name "/USB_DM") (class "Default")
      (node (ref "H1") (pin "2") (pinfunction "D-_2") (pintype "passive"))
      (node (ref "H5") (pin "22") (pinfunction "22_22") (pintype "passive"))
      (node (ref "U2") (pin "68") (pinfunction "USB-DM_68") (pintype "passive"))
    )
    (net (code "74") (name "/USB_DP") (class "Default")
      (node (ref "H1") (pin "3") (pinfunction "D+_3") (pintype "passive"))
      (node (ref "H5") (pin "20") (pinfunction "20_20") (pintype "passive"))
      (node (ref "U2") (pin "69") (pinfunction "USB-DP_69") (pintype "passive"))
    )
    (net (code "75") (name "/USB_ID") (class "Default")
      (node (ref "H1") (pin "4") (pinfunction "ID_4") (pintype "passive"))
      (node (ref "R6") (pin "2") (pinfunction "2_2") (pintype "passive"))
      (node (ref "R9") (pin "1") (pinfunction "1_1") (pintype "passive"))
    )
    (net (code "76") (name "/VRA1") (class "Default")
      (node (ref "C18") (pin "1") (pinfunction "1_1") (pintype "passive"))
      (node (ref "R19") (pin "2") (pinfunction "2_2") (pintype "passive"))
      (node (ref "U2") (pin "81") (pinfunction "VRA1_81") (pintype "passive"))
    )
    (net (code "77") (name "/VRA2") (class "Default")
      (node (ref "C19") (pin "1") (pinfunction "1_1") (pintype "passive"))
      (node (ref "R20") (pin "2") (pinfunction "2_2") (pintype "passive"))
      (node (ref "U2") (pin "83") (pinfunction "VRA2_83") (pintype "passive"))
    )
    (net (code "78") (name "1V1") (class "Default")
      (node (ref "C3") (pin "1") (pinfunction "1_1") (pintype "passive"))
      (node (ref "C30") (pin "1") (pinfunction "1_1") (pintype "passive"))
      (node (ref "C31") (pin "1") (pinfunction "1_1") (pintype "passive"))
      (node (ref "C32") (pin "1") (pinfunction "1_1") (pintype "passive"))
      (node (ref "C4") (pin "1") (pinfunction "1_1") (pintype "passive"))
      (node (ref "L1") (pin "2") (pinfunction "2_2") (pintype "passive"))
      (node (ref "R1") (pin "2") (pinfunction "2_2") (pintype "passive"))
      (node (ref "U2") (pin "22") (pinfunction "VDD-CORE_22") (pintype "passive"))
      (node (ref "U2") (pin "35") (pinfunction "VDD-CORE_35") (pintype "passive"))
      (node (ref "U2") (pin "71") (pinfunction "VDD-CORE_71") (pintype "passive"))
    )
    (net (code "79") (name "2V5") (class "Default")
      (node (ref "C10") (pin "1") (pinfunction "1_1") (pintype "passive"))
      (node (ref "C22") (pin "1") (pinfunction "1_1") (pintype "passive"))
      (node (ref "C26") (pin "1") (pinfunction "1_1") (pintype "passive"))
      (node (ref "C27") (pin "1") (pinfunction "1_1") (pintype "passive"))
      (node (ref "C9") (pin "1") (pinfunction "1_1") (pintype "passive"))
      (node (ref "L2") (pin "2") (pinfunction "2_2") (pintype "passive"))
      (node (ref "R21") (pin "2") (pinfunction "2_2") (pintype "passive"))
      (node (ref "R4") (pin "2") (pinfunction "2_2") (pintype "passive"))
      (node (ref "U2") (pin "30") (pinfunction "VCC-DRAM_30") (pintype "passive"))
      (node (ref "U2") (pin "31") (pinfunction "VCC-DRAM_31") (pintype "passive"))
      (node (ref "U2") (pin "32") (pinfunction "VCC-DRAM_32") (pintype "passive"))
      (node (ref "U2") (pin "34") (pinfunction "VCC-DRAM_34") (pintype "passive"))
      (node (ref "U2") (pin "36") (pinfunction "VCC-DRAM_36") (pintype "passive"))
    )
    (net (code "80") (name "3V0") (class "Default")
      (node (ref "C14") (pin "1") (pinfunction "1_1") (pintype "passive"))
      (node (ref "C15") (pin "1") (pinfunction "1_1") (pintype "passive"))
      (node (ref "H5") (pin "16") (pinfunction "16_16") (pintype "passive"))
      (node (ref "U2") (pin "82") (pinfunction "AGND_82") (pintype "passive"))
      (node (ref "U3") (pin "2") (pinfunction "VOUT_2") (pintype "passive"))
    )
    (net (code "81") (name "3V3") (class "Default")
      (node (ref "C12") (pin "1") (pinfunction "1_1") (pintype "passive"))
      (node (ref "C13") (pin "1") (pinfunction "1_1") (pintype "passive"))
      (node (ref "C20") (pin "1") (pinfunction "1_1") (pintype "passive"))
      (node (ref "C33") (pin "1") (pinfunction "1_1") (pintype "passive"))
      (node (ref "C34") (pin "1") (pinfunction "1_1") (pintype "passive"))
      (node (ref "C35") (pin "1") (pinfunction "1_1") (pintype "passive"))
      (node (ref "H2") (pin "31") (pinfunction "DISP_31") (pintype "passive"))
      (node (ref "H2") (pin "4") (pinfunction "VCC_4") (pintype "passive"))
      (node (ref "H5") (pin "11") (pinfunction "11_11") (pintype "passive"))
      (node (ref "L3") (pin "2") (pinfunction "2_2") (pintype "passive"))
      (node (ref "R10") (pin "1") (pinfunction "1_1") (pintype "passive"))
      (node (ref "R11") (pin "2") (pinfunction "2_2") (pintype "passive"))
      (node (ref "R12") (pin "2") (pinfunction "2_2") (pintype "passive"))
      (node (ref "R13") (pin "2") (pinfunction "2_2") (pintype "passive"))
      (node (ref "R14") (pin "2") (pinfunction "2_2") (pintype "passive"))
      (node (ref "R15") (pin "2") (pinfunction "2_2") (pintype "passive"))
      (node (ref "R17") (pin "1") (pinfunction "1_1") (pintype "passive"))
      (node (ref "R2") (pin "1") (pinfunction "1_1") (pintype "passive"))
      (node (ref "R23") (pin "1") (pinfunction "1_1") (pintype "passive"))
      (node (ref "R6") (pin "1") (pinfunction "1_1") (pintype "passive"))
      (node (ref "R7") (pin "2") (pinfunction "2_2") (pintype "passive"))
      (node (ref "U2") (pin "20") (pinfunction "VCC-IO_20") (pintype "passive"))
      (node (ref "U2") (pin "4") (pinfunction "HPVCC_4") (pintype "passive"))
      (node (ref "U2") (pin "5") (pinfunction "VCCIO_5") (pintype "passive"))
      (node (ref "U2") (pin "50") (pinfunction "VCC-IO_50") (pintype "passive"))
      (node (ref "U2") (pin "67") (pinfunction "UVCC_67") (pintype "passive"))
      (node (ref "U3") (pin "3") (pinfunction "VIN_3") (pintype "passive"))
      (node (ref "U5") (pin "4") (pinfunction "VDD_4") (pintype "passive"))
      (node (ref "U6") (pin "3") (pinfunction "/WP/IO2_3") (pintype "passive"))
      (node (ref "U6") (pin "7") (pinfunction "/HOLD/IO3_7") (pintype "passive"))
      (node (ref "U6") (pin "8") (pinfunction "VCC_8") (pintype "passive"))
      (node (ref "U7") (pin "1") (pinfunction "VDD_1") (pintype "passive"))
    )
    (net (code "82") (name "5V") (class "Default")
      (node (ref "C11") (pin "1") (pinfunction "1_1") (pintype "passive"))
      (node (ref "C17") (pin "2") (pinfunction "2_2") (pintype "passive"))
      (node (ref "C2") (pin "1") (pinfunction "1_1") (pintype "passive"))
      (node (ref "C6") (pin "1") (pinfunction "1_1") (pintype "passive"))
      (node (ref "C8") (pin "1") (pinfunction "1_1") (pintype "passive"))
      (node (ref "H1") (pin "1") (pinfunction "VCC_1") (pintype "passive"))
      (node (ref "H5") (pin "15") (pinfunction "15_15") (pintype "passive"))
      (node (ref "L4") (pin "2") (pinfunction "2_2") (pintype "passive"))
      (node (ref "U1") (pin "10") (pinfunction "VIN1_10") (pintype "passive"))
      (node (ref "U1") (pin "16") (pinfunction "VCC_16") (pintype "passive"))
      (node (ref "U1") (pin "18") (pinfunction "EN3_18") (pintype "passive"))
      (node (ref "U1") (pin "19") (pinfunction "VIN3_19") (pintype "passive"))
      (node (ref "U1") (pin "7") (pinfunction "VIN2_7") (pintype "passive"))
      (node (ref "U1") (pin "8") (pinfunction "EN2_8") (pintype "passive"))
      (node (ref "U1") (pin "9") (pinfunction "EN1_9") (pintype "passive"))
      (node (ref "U4") (pin "6") (pinfunction "IN_6") (pintype "passive"))
    )
    (net (code "83") (name "GND") (class "Default")
      (node (ref "C1") (pin "1") (pinfunction "1_1") (pintype "passive"))
      (node (ref "C11") (pin "2") (pinfunction "2_2") (pintype "passive"))
      (node (ref "C12") (pin "2") (pinfunction "2_2") (pintype "passive"))
      (node (ref "C14") (pin "2") (pinfunction "2_2") (pintype "passive"))
      (node (ref "C15") (pin "2") (pinfunction "2_2") (pintype "passive"))
      (node (ref "C16") (pin "2") (pinfunction "2_2") (pintype "passive"))
      (node (ref "C17") (pin "1") (pinfunction "1_1") (pintype "passive"))
      (node (ref "C18") (pin "2") (pinfunction "2_2") (pintype "passive"))
      (node (ref "C19") (pin "2") (pinfunction "2_2") (pintype "passive"))
      (node (ref "C2") (pin "2") (pinfunction "2_2") (pintype "passive"))
      (node (ref "C20") (pin "2") (pinfunction "2_2") (pintype "passive"))
      (node (ref "C23") (pin "2") (pinfunction "2_2") (pintype "passive"))
      (node (ref "C24") (pin "2") (pinfunction "2_2") (pintype "passive"))
      (node (ref "C25") (pin "2") (pinfunction "2_2") (pintype "passive"))
      (node (ref "C26") (pin "2") (pinfunction "2_2") (pintype "passive"))
      (node (ref "C27") (pin "2") (pinfunction "2_2") (pintype "passive"))
      (node (ref "C28") (pin "2") (pinfunction "2_2") (pintype "passive"))
      (node (ref "C29") (pin "2") (pinfunction "2_2") (pintype "passive"))
      (node (ref "C3") (pin "2") (pinfunction "2_2") (pintype "passive"))
      (node (ref "C30") (pin "2") (pinfunction "2_2") (pintype "passive"))
      (node (ref "C31") (pin "2") (pinfunction "2_2") (pintype "passive"))
      (node (ref "C32") (pin "2") (pinfunction "2_2") (pintype "passive"))
      (node (ref "C33") (pin "2") (pinfunction "2_2") (pintype "passive"))
      (node (ref "C34") (pin "2") (pinfunction "2_2") (pintype "passive"))
      (node (ref "C35") (pin "2") (pinfunction "2_2") (pintype "passive"))
      (node (ref "C5") (pin "2") (pinfunction "2_2") (pintype "passive"))
      (node (ref "C6") (pin "2") (pinfunction "2_2") (pintype "passive"))
      (node (ref "C7") (pin "2") (pinfunction "2_2") (pintype "passive"))
      (node (ref "C8") (pin "2") (pinfunction "2_2") (pintype "passive"))
      (node (ref "C9") (pin "2") (pinfunction "2_2") (pintype "passive"))
      (node (ref "H1") (pin "5") (pinfunction "GND_5") (pintype "passive"))
      (node (ref "H1") (pin "6") (pinfunction "GND_6") (pintype "passive"))
      (node (ref "H1") (pin "7") (pinfunction "GND_7") (pintype "passive"))
      (node (ref "H1") (pin "8") (pinfunction "GND_8") (pintype "passive"))
      (node (ref "H1") (pin "9") (pinfunction "GND_9") (pintype "passive"))
      (node (ref "H2") (pin "13") (pinfunction "G0_13") (pintype "passive"))
      (node (ref "H2") (pin "14") (pinfunction "G1_14") (pintype "passive"))
      (node (ref "H2") (pin "21") (pinfunction "B0_21") (pintype "passive"))
      (node (ref "H2") (pin "22") (pinfunction "B1_22") (pintype "passive"))
      (node (ref "H2") (pin "29") (pinfunction "GND_29") (pintype "passive"))
      (node (ref "H2") (pin "3") (pinfunction "GND_3") (pintype "passive"))
      (node (ref "H2") (pin "36") (pinfunction "GND_36") (pintype "passive"))
      (node (ref "H2") (pin "41") (pinfunction "PAD1_41") (pintype "passive"))
      (node (ref "H2") (pin "42") (pinfunction "PAD2_42") (pintype "passive"))
      (node (ref "H2") (pin "5") (pinfunction "R0_5") (pintype "passive"))
      (node (ref "H2") (pin "6") (pinfunction "R1_6") (pintype "passive"))
      (node (ref "H5") (pin "13") (pinfunction "13_13") (pintype "passive"))
      (node (ref "R18") (pin "1") (pinfunction "1_1") (pintype "passive"))
      (node (ref "R19") (pin "1") (pinfunction "1_1") (pintype "passive"))
      (node (ref "R20") (pin "1") (pinfunction "1_1") (pintype "passive"))
      (node (ref "R22") (pin "1") (pinfunction "1_1") (pintype "passive"))
      (node (ref "R3") (pin "1") (pinfunction "1_1") (pintype "passive"))
      (node (ref "R5") (pin "1") (pinfunction "1_1") (pintype "passive"))
      (node (ref "R8") (pin "1") (pinfunction "1_1") (pintype "passive"))
      (node (ref "U1") (pin "1") (pinfunction "GND3_1") (pintype "passive"))
      (node (ref "U1") (pin "12") (pinfunction "GND1_12") (pintype "passive"))
      (node (ref "U1") (pin "13") (pinfunction "AGND_13") (pintype "passive"))
      (node (ref "U1") (pin "15") (pinfunction "AGND_15") (pintype "passive"))
      (node (ref "U1") (pin "17") (pinfunction "AGND_17") (pintype "passive"))
      (node (ref "U1") (pin "21") (pinfunction "PAD_21") (pintype "passive"))
      (node (ref "U1") (pin "4") (pinfunction "AGND_4") (pintype "passive"))
      (node (ref "U1") (pin "5") (pinfunction "GND2_5") (pintype "passive"))
      (node (ref "U2") (pin "74") (pinfunction "TVGND_74") (pintype "passive"))
      (node (ref "U2") (pin "80") (pinfunction "AVCC_80") (pintype "passive"))
      (node (ref "U2") (pin "89") (pinfunction "GND_89") (pintype "passive"))
      (node (ref "U3") (pin "1") (pinfunction "GND_1") (pintype "passive"))
      (node (ref "U4") (pin "2") (pinfunction "GND_2") (pintype "passive"))
      (node (ref "U5") (pin "10") (pinfunction "PAD1_10") (pintype "passive"))
      (node (ref "U5") (pin "11") (pinfunction "PAD2_11") (pintype "passive"))
      (node (ref "U5") (pin "12") (pinfunction "PAD3_12") (pintype "passive"))
      (node (ref "U5") (pin "13") (pinfunction "PAD4_13") (pintype "passive"))
      (node (ref "U5") (pin "6") (pinfunction "GND_6") (pintype "passive"))
      (node (ref "U6") (pin "4") (pinfunction "GND_4") (pintype "passive"))
      (node (ref "U7") (pin "6") (pinfunction "GND_6") (pintype "passive"))
      (node (ref "U7") (pin "8") (pinfunction "A0_8") (pintype "passive"))
      (node (ref "X1") (pin "2") (pinfunction "GND_2") (pintype "passive"))
      (node (ref "X1") (pin "4") (pinfunction "GND_4") (pintype "passive"))
    )
    (net (code "84") (name "Net-(D1-A)") (class "Default")
      (node (ref "D1") (pin "1") (pinfunction "A_1") (pintype "passive"))
      (node (ref "L4") (pin "1") (pinfunction "1_1") (pintype "passive"))
      (node (ref "U4") (pin "1") (pinfunction "SW_1") (pintype "passive"))
    )
    (net (code "85") (name "Net-(U1-FB1)") (class "Default")
      (node (ref "C4") (pin "2") (pinfunction "2_2") (pintype "passive"))
      (node (ref "R1") (pin "1") (pinfunction "1_1") (pintype "passive"))
      (node (ref "R3") (pin "2") (pinfunction "2_2") (pintype "passive"))
      (node (ref "U1") (pin "14") (pinfunction "FB1_14") (pintype "passive"))
    )
    (net (code "86") (name "Net-(U1-FB2)") (class "Default")
      (node (ref "C10") (pin "2") (pinfunction "2_2") (pintype "passive"))
      (node (ref "R4") (pin "1") (pinfunction "1_1") (pintype "passive"))
      (node (ref "R5") (pin "2") (pinfunction "2_2") (pintype "passive"))
      (node (ref "U1") (pin "3") (pinfunction "FB2_3") (pintype "passive"))
    )
    (net (code "87") (name "Net-(U1-FB3)") (class "Default")
      (node (ref "C13") (pin "2") (pinfunction "2_2") (pintype "passive"))
      (node (ref "R7") (pin "1") (pinfunction "1_1") (pintype "passive"))
      (node (ref "R8") (pin "2") (pinfunction "2_2") (pintype "passive"))
      (node (ref "U1") (pin "2") (pinfunction "FB3_2") (pintype "passive"))
    )
    (net (code "88") (name "Net-(U1-SW1)") (class "Default")
      (node (ref "L1") (pin "1") (pinfunction "1_1") (pintype "passive"))
      (node (ref "U1") (pin "11") (pinfunction "SW1_11") (pintype "passive"))
    )
    (net (code "89") (name "Net-(U1-SW2)") (class "Default")
      (node (ref "L2") (pin "1") (pinfunction "1_1") (pintype "passive"))
      (node (ref "U1") (pin "6") (pinfunction "SW2_6") (pintype "passive"))
    )
    (net (code "90") (name "Net-(U1-SW3)") (class "Default")
      (node (ref "L3") (pin "1") (pinfunction "1_1") (pintype "passive"))
      (node (ref "U1") (pin "20") (pinfunction "SW3_20") (pintype "passive"))
    )
    (net (code "91") (name "Net-(U4-EN)") (class "Default")
      (node (ref "R16") (pin "2") (pinfunction "2_2") (pintype "passive"))
      (node (ref "R17") (pin "2") (pinfunction "2_2") (pintype "passive"))
      (node (ref "U4") (pin "4") (pinfunction "EN_4") (pintype "passive"))
    )
    (net (code "92") (name "VCC-TV") (class "Default")
      (node (ref "C28") (pin "1") (pinfunction "1_1") (pintype "passive"))
      (node (ref "C29") (pin "1") (pinfunction "1_1") (pintype "passive"))
      (node (ref "R10") (pin "2") (pinfunction "2_2") (pintype "passive"))
      (node (ref "U2") (pin "73") (pinfunction "TV_VCC_73") (pintype "passive"))
    )
    (net (code "93") (name "VLED+") (class "Default")
      (node (ref "C16") (pin "1") (pinfunction "1_1") (pintype "passive"))
      (node (ref "D1") (pin "2") (pinfunction "K_2") (pintype "passive"))
      (node (ref "H2") (pin "2") (pinfunction "LEDA_2") (pintype "passive"))
      (node (ref "U4") (pin "5") (pinfunction "OV_5") (pintype "passive"))
    )
    (net (code "94") (name "VLED-") (class "Default")
      (node (ref "H2") (pin "1") (pinfunction "LEDK_1") (pintype "passive"))
      (node (ref "R18") (pin "2") (pinfunction "2_2") (pintype "passive"))
      (node (ref "U4") (pin "3") (pinfunction "FB_3") (pintype "passive"))
    )
    (net (code "95") (name "unconnected-(H2-NC-Pad35)") (class "Default")
      (node (ref "H2") (pin "35") (pinfunction "NC_35") (pintype "passive"))
    )
    (net (code "96") (name "unconnected-(U5-Sd-Pad9)") (class "Default")
      (node (ref "U5") (pin "9") (pinfunction "Sd_9") (pintype "passive"))
    )
  )
)
